# usb.net
KiCad netlist of a schematic drawn in Altium Designer
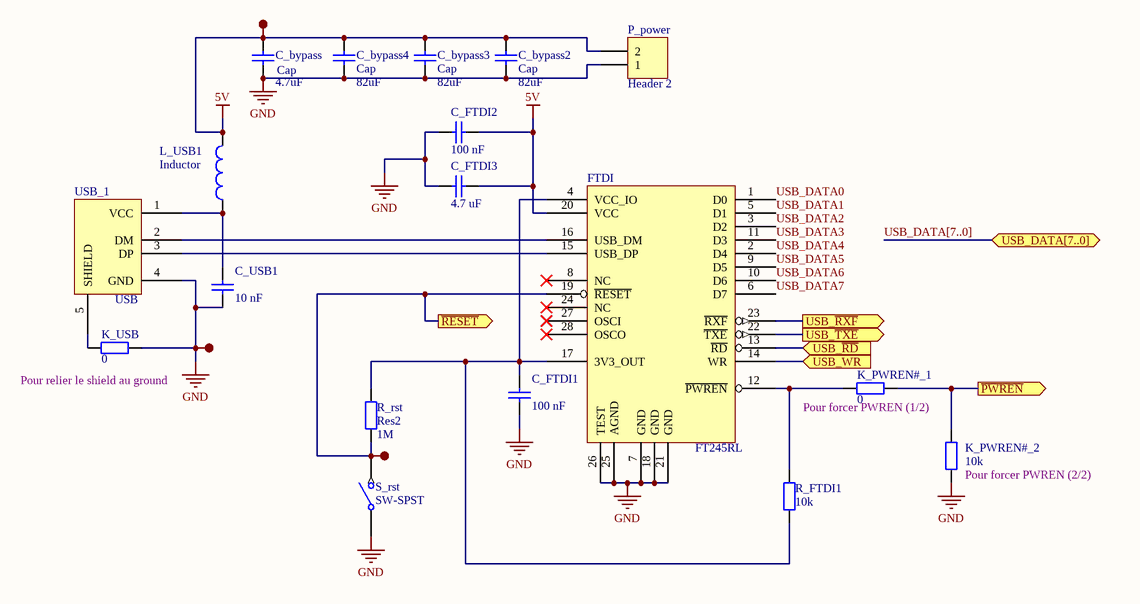
[diagram p0: usb.SchDoc]

(export (version "E")
  (design (tool "Eeschema 10.0.6"))
  (components
    (comp (ref "C_bypass")
      (value "Cap")
      (footprint "ourprints:0805")
      (description "Capacitor")
      (fields (field (name "ALTIUM_VALUE") "4.7uF") (field (name "PUBLISHER") "Altium Limited"))
      (libsource (lib "Miscellaneous Devices") (part "Cap"))
    )
    (comp (ref "C_bypass2")
      (value "Cap")
      (footprint "Capacitor_bypass")
      (description "Capacitor")
      (fields (field (name "ALTIUM_VALUE") "82uF") (field (name "PUBLISHER") "Altium Limited"))
      (libsource (lib "Miscellaneous Devices") (part "Cap"))
    )
    (comp (ref "C_bypass3")
      (value "Cap")
      (footprint "Capacitor_bypass")
      (description "Capacitor")
      (fields (field (name "ALTIUM_VALUE") "82uF") (field (name "PUBLISHER") "Altium Limited"))
      (libsource (lib "Miscellaneous Devices") (part "Cap"))
    )
    (comp (ref "C_bypass4")
      (value "Cap")
      (footprint "Capacitor_bypass")
      (description "Capacitor")
      (fields (field (name "ALTIUM_VALUE") "82uF") (field (name "PUBLISHER") "Altium Limited"))
      (libsource (lib "Miscellaneous Devices") (part "Cap"))
    )
    (comp (ref "C_FTDI1")
      (value "100 nF")
      (footprint "ourprints:0805")
      (description "Capacitor")
      (fields (field (name "Comment") "Cap") (field (name "PUBLISHER") "Altium Limited"))
      (libsource (lib "Miscellaneous Devices") (part "Cap"))
    )
    (comp (ref "C_FTDI2")
      (value "100 nF")
      (footprint "ourprints:0805")
      (description "Capacitor")
      (fields (field (name "Comment") "Cap") (field (name "PUBLISHER") "Altium Limited"))
      (libsource (lib "Miscellaneous Devices") (part "Cap"))
    )
    (comp (ref "C_FTDI3")
      (value "4.7 uF")
      (footprint "ourprints:0805")
      (description "Capacitor")
      (fields (field (name "Comment") "Cap") (field (name "PUBLISHER") "Altium Limited"))
      (libsource (lib "Miscellaneous Devices") (part "Cap"))
    )
    (comp (ref "C_USB1")
      (value "10 nF")
      (footprint "ourprints:0805")
      (description "Capacitor")
      (fields (field (name "Comment") "Cap") (field (name "PUBLISHER") "Altium Limited"))
      (libsource (lib "Miscellaneous Devices") (part "Cap"))
    )
    (comp (ref "FTDI") (value "FT245RL") (footprint "SSOP28") (libsource (lib "ourlibs") (part "FT245RL")))
    (comp (ref "K_PWREN#_1")
      (value "0")
      (footprint "ourprints:0805")
      (description "Resistor")
      (fields (field (name "Comment") "Res2") (field (name "PUBLISHER") "Altium Limited"))
      (libsource (lib "") (part "Res2_1"))
    )
    (comp (ref "K_PWREN#_2")
      (value "10k")
      (footprint "ourprints:0805")
      (description "Resistor")
      (fields (field (name "Comment") "Res2") (field (name "PUBLISHER") "Altium Limited"))
      (libsource (lib "Miscellaneous Devices") (part "Res2"))
    )
    (comp (ref "K_USB")
      (value "0")
      (footprint "ourprints:0805")
      (description "Resistor")
      (fields (field (name "Comment") "Res2") (field (name "PUBLISHER") "Altium Limited"))
      (libsource (lib "") (part "Res2_1"))
    )
    (comp (ref "L_USB1")
      (value "Inductor")
      (footprint "ourprints:0805")
      (fields (field (name "PUBLISHER") "Altium Limited"))
      (libsource (lib "Miscellaneous Devices") (part "Inductor"))
    )
    (comp (ref "P_power")
      (value "Header 2")
      (footprint "HDR1X2")
      (description "Header, 2-Pin")
      (fields (field (name "PUBLISHER") "Altium Limited"))
      (libsource (lib "Miscellaneous Connectors") (part "Header 2"))
    )
    (comp (ref "R_FTDI1")
      (value "10k")
      (footprint "ourprints:0805")
      (description "Resistor")
      (fields (field (name "Comment") "Res2") (field (name "PUBLISHER") "Altium Limited"))
      (libsource (lib "Miscellaneous Devices") (part "Res2"))
    )
    (comp (ref "R_rst")
      (value "Res2")
      (footprint "ourprints:0805")
      (description "Resistor")
      (fields (field (name "ALTIUM_VALUE") "1M") (field (name "PUBLISHER") "Altium Limited"))
      (libsource (lib "") (part "Res2_2"))
    )
    (comp (ref "S_rst")
      (value "SW-SPST")
      (footprint "0805")
      (description "Single-Pole, Single-Throw Switch")
      (fields (field (name "PUBLISHER") "Altium Limited"))
      (libsource (lib "Miscellaneous Devices") (part "SW-SPST"))
    )
    (comp (ref "TP_5v")
      (value "TestPoint")
      (footprint "testpoint")
      (libsource (lib "ourlibs") (part "TestPoint"))
    )
    (comp (ref "TP_gnd")
      (value "TestPoint")
      (footprint "testpoint")
      (libsource (lib "ourlibs") (part "TestPoint"))
    )
    (comp (ref "TP_reset")
      (value "TestPoint")
      (footprint "testpoint")
      (libsource (lib "ourlibs") (part "TestPoint"))
    )
    (comp (ref "USB_1") (value "USB") (footprint "USB2.5-2H4E") (libsource (lib "ourlibs") (part "USB")))
  )
  (nets
    (net (code "1") (name "/USB_DATA0") (class "Default")
      (node (ref "FTDI") (pin "1") (pinfunction "D0_1") (pintype "passive"))
    )
    (net (code "2") (name "/USB_DATA1") (class "Default")
      (node (ref "FTDI") (pin "5") (pinfunction "D1_5") (pintype "passive"))
    )
    (net (code "3") (name "/USB_DATA2") (class "Default")
      (node (ref "FTDI") (pin "3") (pinfunction "D2_3") (pintype "passive"))
    )
    (net (code "4") (name "/USB_DATA3") (class "Default")
      (node (ref "FTDI") (pin "11") (pinfunction "D3_11") (pintype "passive"))
    )
    (net (code "5") (name "/USB_DATA4") (class "Default")
      (node (ref "FTDI") (pin "2") (pinfunction "D4_2") (pintype "passive"))
    )
    (net (code "6") (name "/USB_DATA5") (class "Default")
      (node (ref "FTDI") (pin "9") (pinfunction "D5_9") (pintype "passive"))
    )
    (net (code "7") (name "/USB_DATA6") (class "Default")
      (node (ref "FTDI") (pin "10") (pinfunction "D6_10") (pintype "passive"))
    )
    (net (code "8") (name "/USB_DATA7") (class "Default")
      (node (ref "FTDI") (pin "6") (pinfunction "D7_6") (pintype "passive"))
    )
    (net (code "10") (name "/USB_WR") (class "Default")
      (node (ref "FTDI") (pin "14") (pinfunction "WR_14") (pintype "passive"))
    )
    (net (code "11") (name "/USB_~{RD}") (class "Default")
      (node (ref "FTDI") (pin "13") (pinfunction "~{RD}_13") (pintype "passive"))
    )
    (net (code "12") (name "/USB_~{RXF}") (class "Default")
      (node (ref "FTDI") (pin "23") (pinfunction "~{RXF}_23") (pintype "output"))
    )
    (net (code "13") (name "/USB_~{TXE}") (class "Default")
      (node (ref "FTDI") (pin "22") (pinfunction "~{TXE}_22") (pintype "output"))
    )
    (net (code "14") (name "/~{PWREN}") (class "Default")
      (node (ref "K_PWREN#_1") (pin "2") (pinfunction "2_2") (pintype "passive"))
      (node (ref "K_PWREN#_2") (pin "1") (pinfunction "1_1") (pintype "passive"))
    )
    (net (code "15") (name "/~{RESET}") (class "Default")
      (node (ref "FTDI") (pin "19") (pinfunction "~{RESET}_19") (pintype "passive"))
      (node (ref "R_rst") (pin "1") (pinfunction "1_1") (pintype "passive"))
      (node (ref "S_rst") (pin "2") (pinfunction "NO_2") (pintype "output"))
      (node (ref "TP_reset") (pin "1") (pinfunction "TP_1") (pintype "passive"))
    )
    (net (code "16") (name "5V") (class "Default")
      (node (ref "C_FTDI2") (pin "2") (pinfunction "2_2") (pintype "passive"))
      (node (ref "C_FTDI3") (pin "2") (pinfunction "2_2") (pintype "passive"))
      (node (ref "C_bypass") (pin "1") (pinfunction "1_1") (pintype "passive"))
      (node (ref "C_bypass2") (pin "1") (pinfunction "1_1") (pintype "passive"))
      (node (ref "C_bypass3") (pin "1") (pinfunction "1_1") (pintype "passive"))
      (node (ref "C_bypass4") (pin "1") (pinfunction "1_1") (pintype "passive"))
      (node (ref "FTDI") (pin "20") (pinfunction "VCC_20") (pintype "passive"))
      (node (ref "L_USB1") (pin "2") (pinfunction "2_2") (pintype "passive"))
      (node (ref "P_power") (pin "2") (pinfunction "2_2") (pintype "passive"))
      (node (ref "TP_5v") (pin "1") (pinfunction "TP_1") (pintype "passive"))
    )
    (net (code "17") (name "GND") (class "Default")
      (node (ref "C_FTDI1") (pin "2") (pinfunction "2_2") (pintype "passive"))
      (node (ref "C_FTDI2") (pin "1") (pinfunction "1_1") (pintype "passive"))
      (node (ref "C_FTDI3") (pin "1") (pinfunction "1_1") (pintype "passive"))
      (node (ref "C_USB1") (pin "2") (pinfunction "2_2") (pintype "passive"))
      (node (ref "C_bypass") (pin "2") (pinfunction "2_2") (pintype "passive"))
      (node (ref "C_bypass2") (pin "2") (pinfunction "2_2") (pintype "passive"))
      (node (ref "C_bypass3") (pin "2") (pinfunction "2_2") (pintype "passive"))
      (node (ref "C_bypass4") (pin "2") (pinfunction "2_2") (pintype "passive"))
      (node (ref "FTDI") (pin "18") (pinfunction "GND_18") (pintype "passive"))
      (node (ref "FTDI") (pin "21") (pinfunction "GND_21") (pintype "passive"))
      (node (ref "FTDI") (pin "25") (pinfunction "AGND_25") (pintype "passive"))
      (node (ref "FTDI") (pin "26") (pinfunction "TEST_26") (pintype "passive"))
      (node (ref "FTDI") (pin "7") (pinfunction "GND_7") (pintype "passive"))
      (node (ref "K_PWREN#_2") (pin "2") (pinfunction "2_2") (pintype "passive"))
      (node (ref "K_USB") (pin "2") (pinfunction "2_2") (pintype "passive"))
      (node (ref "P_power") (pin "1") (pinfunction "1_1") (pintype "passive"))
      (node (ref "S_rst") (pin "1") (pinfunction "COMMON_1") (pintype "passive"))
      (node (ref "TP_gnd") (pin "1") (pinfunction "TP_1") (pintype "passive"))
      (node (ref "USB_1") (pin "4") (pinfunction "GND_4") (pintype "passive"))
    )
    (net (code "18") (name "Net-(FTDI-3V3_OUT)") (class "Default")
      (node (ref "C_FTDI1") (pin "1") (pinfunction "1_1") (pintype "passive"))
      (node (ref "FTDI") (pin "17") (pinfunction "3V3_OUT_17") (pintype "passive"))
      (node (ref "FTDI") (pin "4") (pinfunction "VCC_IO_4") (pintype "passive"))
      (node (ref "R_FTDI1") (pin "2") (pinfunction "2_2") (pintype "passive"))
      (node (ref "R_rst") (pin "2") (pinfunction "2_2") (pintype "passive"))
    )
    (net (code "19") (name "Net-(FTDI-USB_DM)") (class "Default")
      (node (ref "FTDI") (pin "16") (pinfunction "USB_DM_16") (pintype "passive"))
      (node (ref "USB_1") (pin "2") (pinfunction "DM_2") (pintype "passive"))
    )
    (net (code "20") (name "Net-(FTDI-USB_DP)") (class "Default")
      (node (ref "FTDI") (pin "15") (pinfunction "USB_DP_15") (pintype "passive"))
      (node (ref "USB_1") (pin "3") (pinfunction "DP_3") (pintype "passive"))
    )
    (net (code "21") (name "Net-(FTDI-~{PWREN})") (class "Default")
      (node (ref "FTDI") (pin "12") (pinfunction "~{PWREN}_12") (pintype "passive"))
      (node (ref "K_PWREN#_1") (pin "1") (pinfunction "1_1") (pintype "passive"))
      (node (ref "R_FTDI1") (pin "1") (pinfunction "1_1") (pintype "passive"))
    )
    (net (code "22") (name "Net-(USB_1-SHIELD)") (class "Default")
      (node (ref "K_USB") (pin "1") (pinfunction "1_1") (pintype "passive"))
      (node (ref "USB_1") (pin "5") (pinfunction "SHIELD_5") (pintype "passive"))
    )
    (net (code "23") (name "Net-(USB_1-VCC)") (class "Default")
      (node (ref "C_USB1") (pin "1") (pinfunction "1_1") (pintype "passive"))
      (node (ref "L_USB1") (pin "1") (pinfunction "1_1") (pintype "passive"))
      (node (ref "USB_1") (pin "1") (pinfunction "VCC_1") (pintype "passive"))
    )
    (net (code "24") (name "unconnected-(FTDI-NC-Pad8)") (class "Default")
      (node (ref "FTDI") (pin "8") (pinfunction "NC_8") (pintype "passive+no_connect"))
    )
    (net (code "25") (name "unconnected-(FTDI-NC-Pad24)") (class "Default")
      (node (ref "FTDI") (pin "24") (pinfunction "NC_24") (pintype "passive+no_connect"))
    )
    (net (code "26") (name "unconnected-(FTDI-OSCI-Pad27)") (class "Default")
      (node (ref "FTDI") (pin "27") (pinfunction "OSCI_27") (pintype "passive+no_connect"))
    )
    (net (code "27") (name "unconnected-(FTDI-OSCO-Pad28)") (class "Default")
      (node (ref "FTDI") (pin "28") (pinfunction "OSCO_28") (pintype "passive+no_connect"))
    )
  )
)
